# NEW.net
KiCad netlist of a schematic drawn in EAGLE
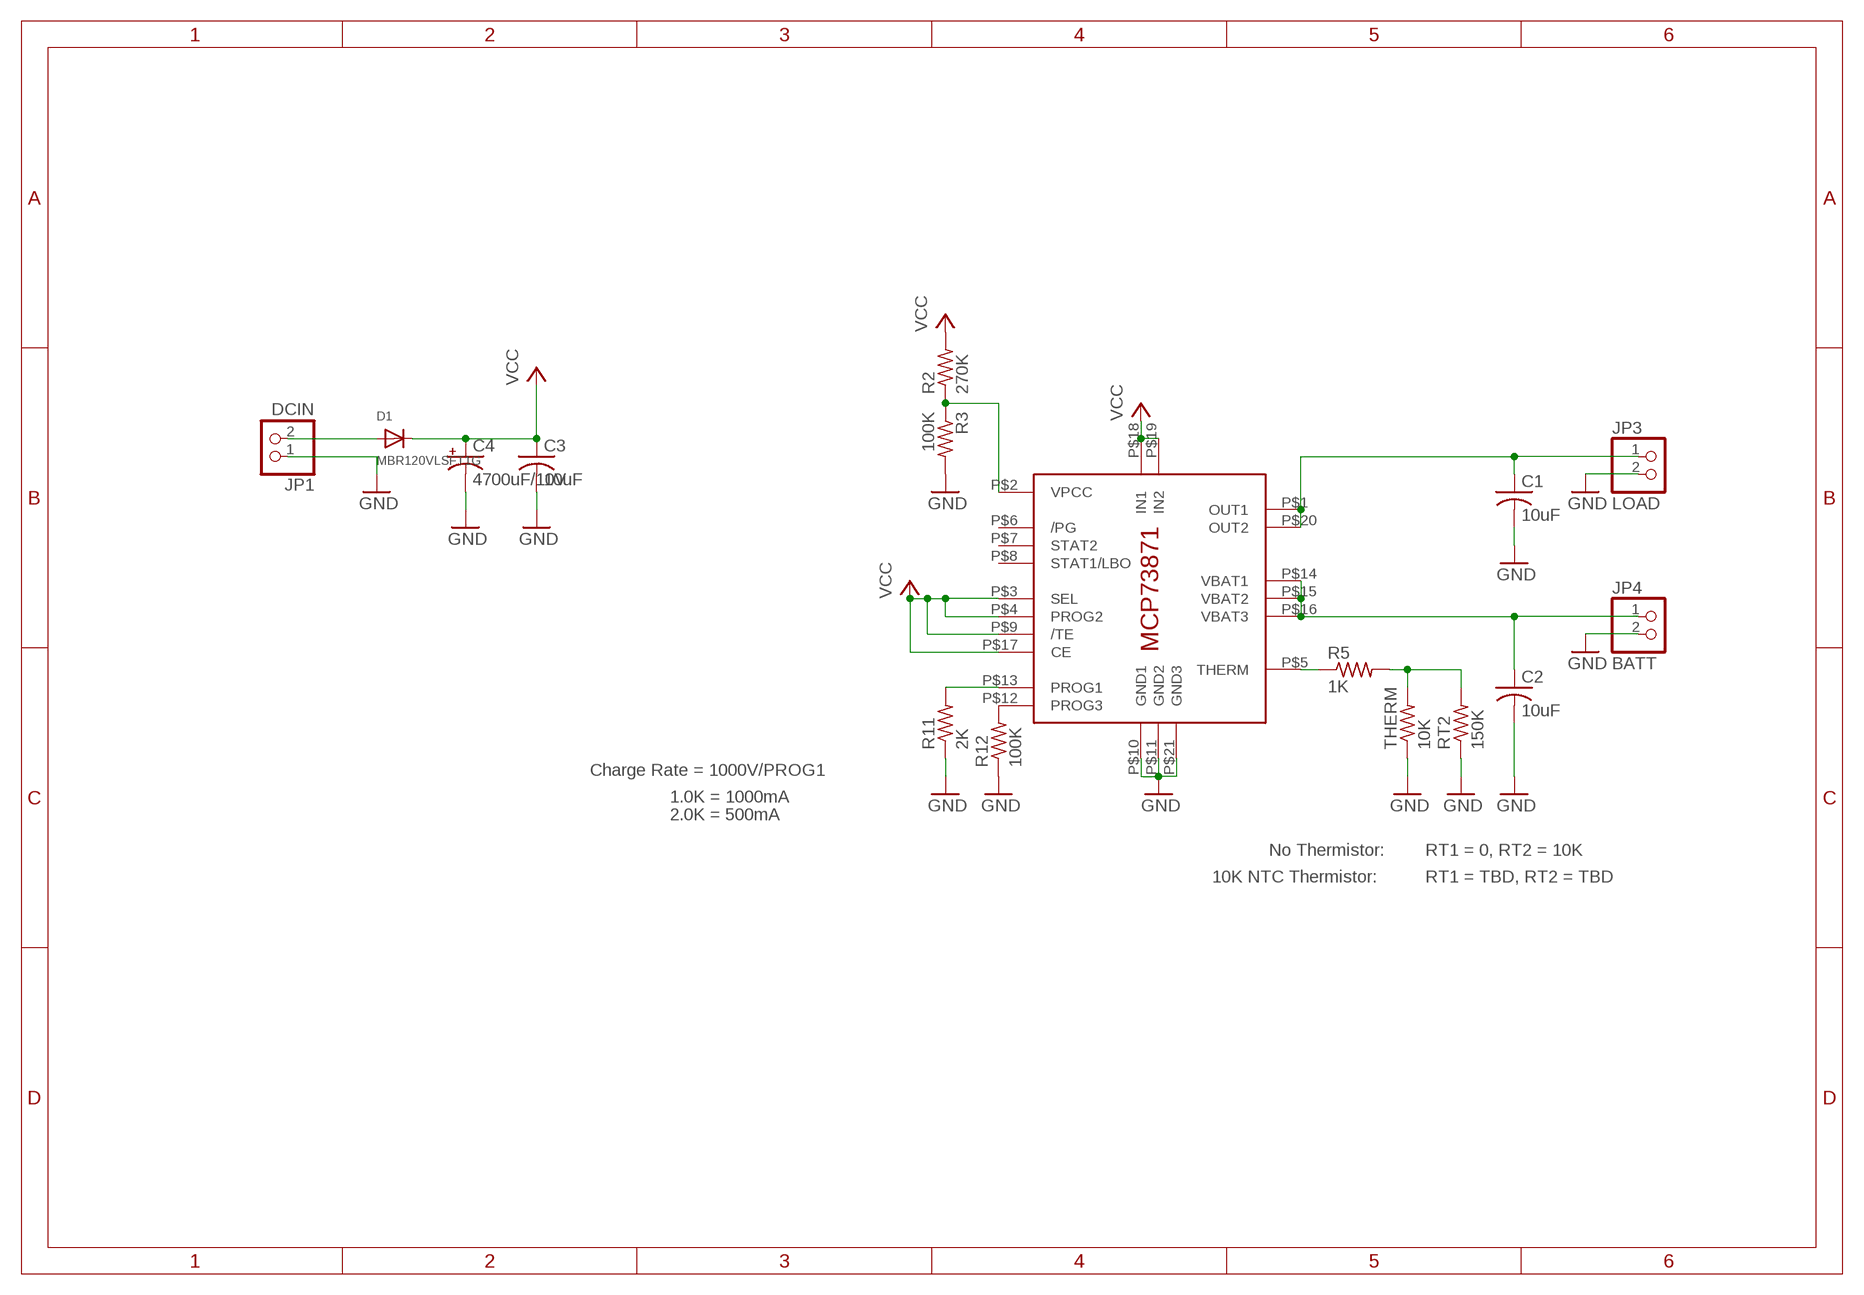
[diagram p0: schematic, sheet 1]

(export (version "E")
  (design (tool "Eeschema 10.0.6"))
  (components
    (comp (ref "C1")
      (value "10uF")
      (footprint "eagle-import:C0805K")
      (libsource (lib "eagle-import") (part "C-USC0805K"))
    )
    (comp (ref "C2")
      (value "10uF")
      (footprint "eagle-import:C0805K")
      (libsource (lib "eagle-import") (part "C-USC0805K"))
    )
    (comp (ref "C3")
      (value "10uF")
      (footprint "eagle-import:C0805K")
      (libsource (lib "eagle-import") (part "C-USC0805K"))
    )
    (comp (ref "C4")
      (value "4700uF/10V")
      (footprint "eagle-import:E5-10,5")
      (libsource (lib "eagle-import") (part "CPOL-USE5-10.5"))
    )
    (comp (ref "D1")
      (value "MBR120VLSFT1G")
      (footprint "eagle-import:SOD-123")
      (libsource (lib "eagle-import") (part "DIODESOD-123"))
    )
    (comp (ref "IC1")
      (value "MCP73871")
      (footprint "eagle-import:QFN20_4MM")
      (libsource (lib "eagle-import") (part "MCP73871"))
    )
    (comp (ref "JP1")
      (value "DCIN")
      (footprint "eagle-import:1X02_OVAL")
      (libsource (lib "eagle-import") (part "HEADER-1X2"))
    )
    (comp (ref "JP3")
      (value "LOAD")
      (footprint "eagle-import:1X02_ROUND")
      (libsource (lib "eagle-import") (part "HEADER-1X2ROUND"))
    )
    (comp (ref "JP4")
      (value "BATT")
      (footprint "eagle-import:1X02_ROUND")
      (libsource (lib "eagle-import") (part "HEADER-1X2ROUND"))
    )
    (comp (ref "R2")
      (value "270K")
      (footprint "eagle-import:R0805")
      (libsource (lib "eagle-import") (part "R-US_R0805"))
    )
    (comp (ref "R3")
      (value "100K")
      (footprint "eagle-import:R0805")
      (libsource (lib "eagle-import") (part "R-US_R0805"))
    )
    (comp (ref "R5")
      (value "1K")
      (footprint "eagle-import:M0805")
      (libsource (lib "eagle-import") (part "R-US_M0805"))
    )
    (comp (ref "R11")
      (value "2K")
      (footprint "eagle-import:M0805")
      (libsource (lib "eagle-import") (part "R-US_M0805"))
    )
    (comp (ref "R12")
      (value "100K")
      (footprint "eagle-import:R0805")
      (libsource (lib "eagle-import") (part "R-US_R0805"))
    )
    (comp (ref "RT2")
      (value "150K")
      (footprint "eagle-import:M0805")
      (libsource (lib "eagle-import") (part "R-US_M0805"))
    )
    (comp (ref "THERM")
      (value "10K")
      (footprint "eagle-import:M0805")
      (libsource (lib "eagle-import") (part "R-US_M0805"))
    )
  )
  (nets
    (net (code "1") (name "GND") (class "Default")
      (node (ref "C1") (pin "2") (pinfunction "2_2") (pintype "passive"))
      (node (ref "C2") (pin "2") (pinfunction "2_2") (pintype "passive"))
      (node (ref "C3") (pin "2") (pinfunction "2_2") (pintype "passive"))
      (node (ref "C4") (pin "-") (pinfunction "-_-") (pintype "passive"))
      (node (ref "IC1") (pin "P$10") (pinfunction "GND1_P$10") (pintype "power_in"))
      (node (ref "IC1") (pin "P$11") (pinfunction "GND2_P$11") (pintype "power_in"))
      (node (ref "IC1") (pin "P$21") (pinfunction "GND3_P$21") (pintype "power_in"))
      (node (ref "JP1") (pin "1") (pinfunction "1_1") (pintype "passive"))
      (node (ref "JP3") (pin "2") (pinfunction "2_2") (pintype "passive"))
      (node (ref "JP4") (pin "2") (pinfunction "2_2") (pintype "passive"))
      (node (ref "R11") (pin "1") (pinfunction "1_1") (pintype "passive"))
      (node (ref "R12") (pin "1") (pinfunction "1_1") (pintype "passive"))
      (node (ref "R3") (pin "2") (pinfunction "2_2") (pintype "passive"))
      (node (ref "RT2") (pin "1") (pinfunction "1_1") (pintype "passive"))
      (node (ref "THERM") (pin "1") (pinfunction "1_1") (pintype "passive"))
    )
    (net (code "2") (name "Net-(D1-PadA)") (class "Default")
      (node (ref "D1") (pin "A") (pinfunction "A_A") (pintype "passive"))
      (node (ref "JP1") (pin "2") (pinfunction "2_2") (pintype "passive"))
    )
    (net (code "3") (name "Net-(IC1-OUT1)") (class "Default")
      (node (ref "C1") (pin "1") (pinfunction "1_1") (pintype "passive"))
      (node (ref "IC1") (pin "P$1") (pinfunction "OUT1_P$1") (pintype "output"))
      (node (ref "IC1") (pin "P$20") (pinfunction "OUT2_P$20") (pintype "output"))
      (node (ref "JP3") (pin "1") (pinfunction "1_1") (pintype "passive"))
    )
    (net (code "4") (name "Net-(IC1-PROG1)") (class "Default")
      (node (ref "IC1") (pin "P$13") (pinfunction "PROG1_P$13") (pintype "input"))
      (node (ref "R11") (pin "2") (pinfunction "2_2") (pintype "passive"))
    )
    (net (code "5") (name "Net-(IC1-PROG3)") (class "Default")
      (node (ref "IC1") (pin "P$12") (pinfunction "PROG3_P$12") (pintype "input"))
      (node (ref "R12") (pin "2") (pinfunction "2_2") (pintype "passive"))
    )
    (net (code "6") (name "Net-(IC1-THERM)") (class "Default")
      (node (ref "IC1") (pin "P$5") (pinfunction "THERM_P$5") (pintype "input"))
      (node (ref "R5") (pin "1") (pinfunction "1_1") (pintype "passive"))
    )
    (net (code "7") (name "Net-(IC1-VBAT1)") (class "Default")
      (node (ref "C2") (pin "1") (pinfunction "1_1") (pintype "passive"))
      (node (ref "IC1") (pin "P$14") (pinfunction "VBAT1_P$14") (pintype "output"))
      (node (ref "IC1") (pin "P$15") (pinfunction "VBAT2_P$15") (pintype "output"))
      (node (ref "IC1") (pin "P$16") (pinfunction "VBAT3_P$16") (pintype "output"))
      (node (ref "JP4") (pin "1") (pinfunction "1_1") (pintype "passive"))
    )
    (net (code "8") (name "Net-(IC1-VPCC)") (class "Default")
      (node (ref "IC1") (pin "P$2") (pinfunction "VPCC_P$2") (pintype "input"))
      (node (ref "R2") (pin "1") (pinfunction "1_1") (pintype "passive"))
      (node (ref "R3") (pin "1") (pinfunction "1_1") (pintype "passive"))
    )
    (net (code "9") (name "Net-(R5-Pad2)") (class "Default")
      (node (ref "R5") (pin "2") (pinfunction "2_2") (pintype "passive"))
      (node (ref "RT2") (pin "2") (pinfunction "2_2") (pintype "passive"))
      (node (ref "THERM") (pin "2") (pinfunction "2_2") (pintype "passive"))
    )
    (net (code "10") (name "VCC") (class "Default")
      (node (ref "C3") (pin "1") (pinfunction "1_1") (pintype "passive"))
      (node (ref "C4") (pin "+") (pinfunction "+_+") (pintype "passive"))
      (node (ref "D1") (pin "C") (pinfunction "C_C") (pintype "passive"))
      (node (ref "IC1") (pin "P$17") (pinfunction "CE_P$17") (pintype "input"))
      (node (ref "IC1") (pin "P$18") (pinfunction "IN1_P$18") (pintype "input"))
      (node (ref "IC1") (pin "P$19") (pinfunction "IN2_P$19") (pintype "input"))
      (node (ref "IC1") (pin "P$3") (pinfunction "SEL_P$3") (pintype "input"))
      (node (ref "IC1") (pin "P$4") (pinfunction "PROG2_P$4") (pintype "input"))
      (node (ref "IC1") (pin "P$9") (pinfunction "/TE_P$9") (pintype "input"))
      (node (ref "R2") (pin "2") (pinfunction "2_2") (pintype "passive"))
    )
    (net (code "11") (name "unconnected-(IC1-STAT1{slash}LBO-PadP$8)") (class "Default")
      (node (ref "IC1") (pin "P$8") (pinfunction "STAT1/LBO_P$8") (pintype "output"))
    )
    (net (code "12") (name "unconnected-(IC1-STAT2-PadP$7)") (class "Default")
      (node (ref "IC1") (pin "P$7") (pinfunction "STAT2_P$7") (pintype "output"))
    )
    (net (code "13") (name "unconnected-(IC1-{slash}PG-PadP$6)") (class "Default")
      (node (ref "IC1") (pin "P$6") (pinfunction "/PG_P$6") (pintype "output"))
    )
  )
)
